# RJ11-shield.net
KiCad netlist of a schematic drawn in EAGLE
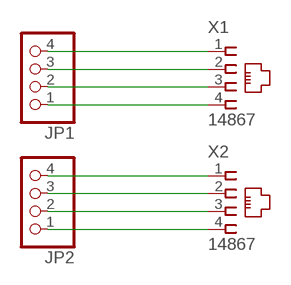
[diagram p0: schematic, sheet 1]

(export (version "E")
  (design (tool "Eeschema 10.0.6"))
  (components
    (comp (ref "JP1")
      (value "PINHD-1X4")
      (footprint "eagle-import:1X04")
      (libsource (lib "eagle-import") (part "PINHD-1X4"))
    )
    (comp (ref "JP2")
      (value "PINHD-1X4")
      (footprint "eagle-import:1X04")
      (libsource (lib "eagle-import") (part "PINHD-1X4"))
    )
    (comp (ref "X1")
      (value "14867")
      (footprint "eagle-import:14867")
      (libsource (lib "eagle-import") (part "14867"))
    )
    (comp (ref "X2")
      (value "14867")
      (footprint "eagle-import:14867")
      (libsource (lib "eagle-import") (part "14867"))
    )
  )
  (nets
    (net (code "1") (name "Net-(JP1-Pad1)") (class "Default")
      (node (ref "JP1") (pin "1") (pinfunction "1_1") (pintype "passive"))
      (node (ref "X1") (pin "4") (pinfunction "4_4") (pintype "passive"))
    )
    (net (code "2") (name "Net-(JP1-Pad2)") (class "Default")
      (node (ref "JP1") (pin "2") (pinfunction "2_2") (pintype "passive"))
      (node (ref "X1") (pin "3") (pinfunction "3_3") (pintype "passive"))
    )
    (net (code "3") (name "Net-(JP1-Pad3)") (class "Default")
      (node (ref "JP1") (pin "3") (pinfunction "3_3") (pintype "passive"))
      (node (ref "X1") (pin "2") (pinfunction "2_2") (pintype "passive"))
    )
    (net (code "4") (name "Net-(JP1-Pad4)") (class "Default")
      (node (ref "JP1") (pin "4") (pinfunction "4_4") (pintype "passive"))
      (node (ref "X1") (pin "1") (pinfunction "1_1") (pintype "passive"))
    )
    (net (code "5") (name "Net-(JP2-Pad1)") (class "Default")
      (node (ref "JP2") (pin "1") (pinfunction "1_1") (pintype "passive"))
      (node (ref "X2") (pin "4") (pinfunction "4_4") (pintype "passive"))
    )
    (net (code "6") (name "Net-(JP2-Pad2)") (class "Default")
      (node (ref "JP2") (pin "2") (pinfunction "2_2") (pintype "passive"))
      (node (ref "X2") (pin "3") (pinfunction "3_3") (pintype "passive"))
    )
    (net (code "7") (name "Net-(JP2-Pad3)") (class "Default")
      (node (ref "JP2") (pin "3") (pinfunction "3_3") (pintype "passive"))
      (node (ref "X2") (pin "2") (pinfunction "2_2") (pintype "passive"))
    )
    (net (code "8") (name "Net-(JP2-Pad4)") (class "Default")
      (node (ref "JP2") (pin "4") (pinfunction "4_4") (pintype "passive"))
      (node (ref "X2") (pin "1") (pinfunction "1_1") (pintype "passive"))
    )
  )
)
